# C-01_CPU_PWR.net
KiCad netlist of a schematic drawn in Altium Designer
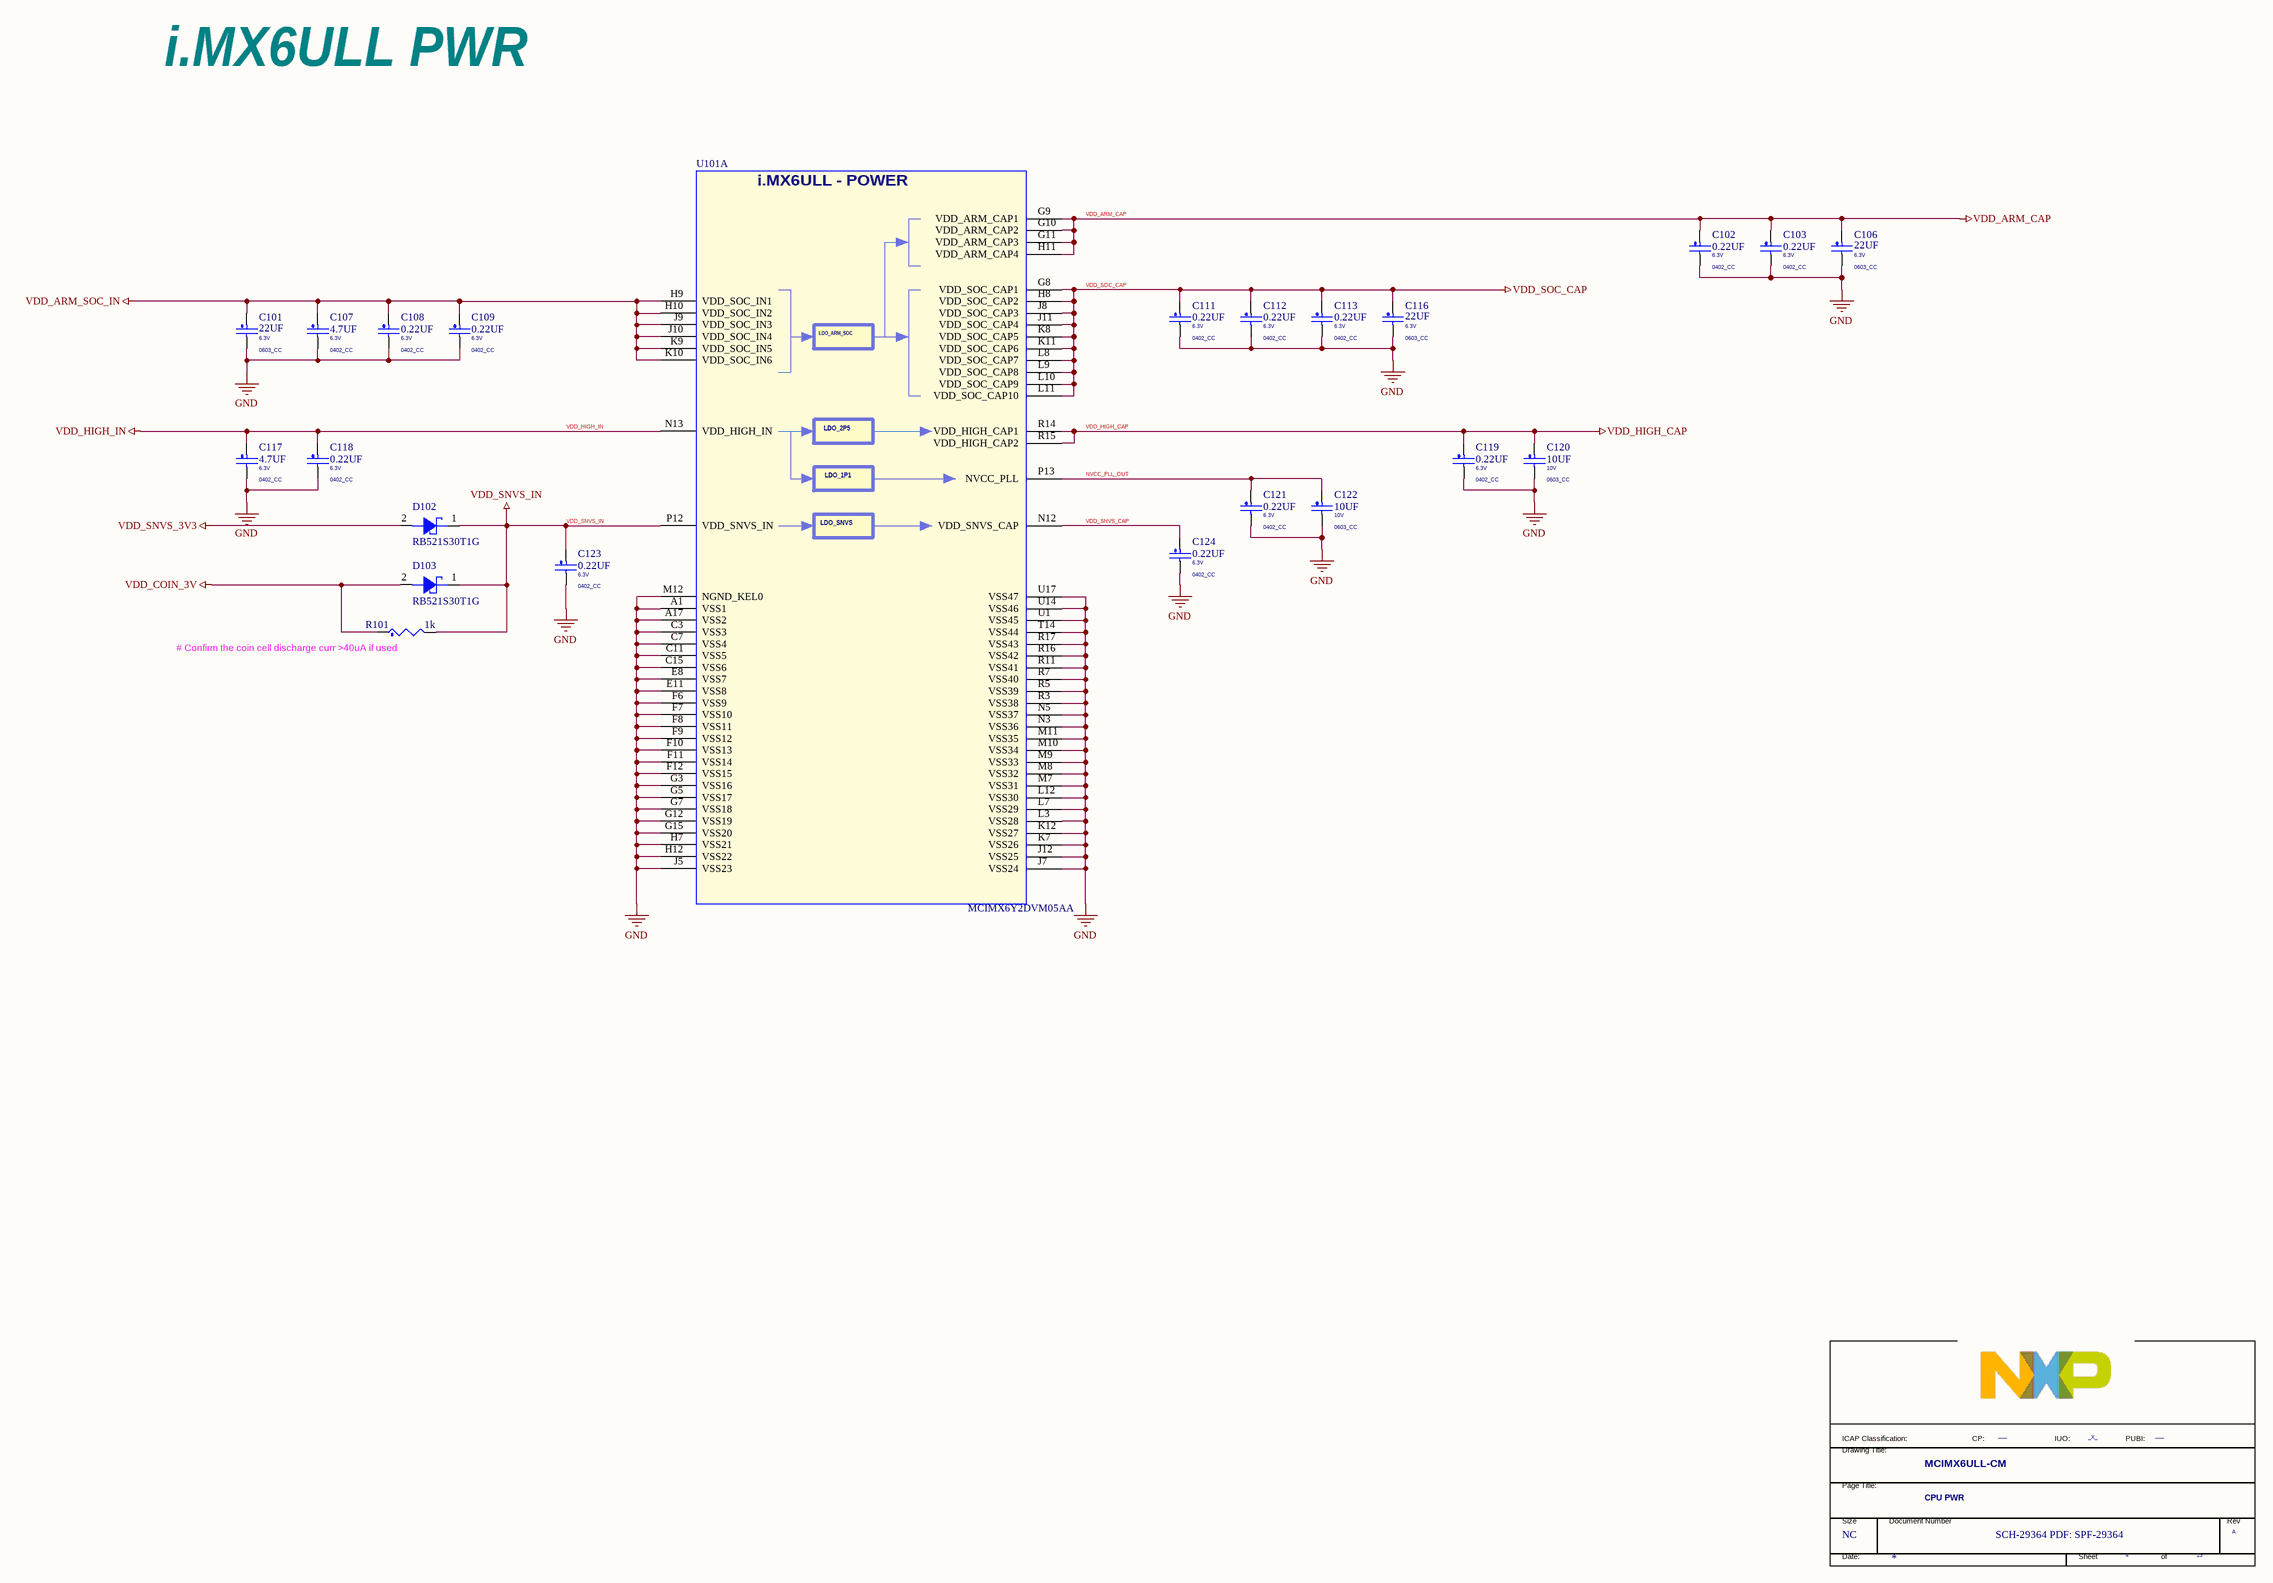
[diagram p0: C-01 CPU PWR.SchDoc]

(export (version "E")
  (design (tool "Eeschema 10.0.6"))
  (components
    (comp (ref "C101")
      (value "22UF")
      (footprint "C0603_H0.8mm")
      (description "CAP CER 22UF 6.3V 20% X5R 0603")
      (fields
        (field (name "VOLTAGE") "6.3V")
        (field (name "TOLERANCE") "20%")
        (field (name "VOLTAGE RATING") "6.3V")
        (field (name "PCB FOOTPRINT") "0603_CC")
      )
      (libsource (lib "*") (part "CAP_NP"))
    )
    (comp (ref "C102")
      (value "0.22UF")
      (footprint "C0402_H0.5mm")
      (description "CAP CER 0.22UF 6.3V 20% X5R 0402")
      (fields
        (field (name "VOLTAGE") "6.3V")
        (field (name "TOLERANCE") "20%")
        (field (name "PCB FOOTPRINT") "0402_CC")
      )
      (libsource (lib "*") (part "CAP_NP"))
    )
    (comp (ref "C103")
      (value "0.22UF")
      (footprint "C0402_H0.5mm")
      (description "CAP CER 0.22UF 6.3V 20% X5R 0402")
      (fields
        (field (name "VOLTAGE") "6.3V")
        (field (name "TOLERANCE") "20%")
        (field (name "PCB FOOTPRINT") "0402_CC")
      )
      (libsource (lib "*") (part "CAP_NP"))
    )
    (comp (ref "C106")
      (value "22UF")
      (footprint "C0603_H0.8mm")
      (description "CAP CER 22UF 6.3V 20% X5R 0603")
      (fields
        (field (name "VOLTAGE") "6.3V")
        (field (name "TOLERANCE") "20%")
        (field (name "PCB FOOTPRINT") "0603_CC")
      )
      (libsource (lib "*") (part "CAP_NP"))
    )
    (comp (ref "C107")
      (value "4.7UF")
      (footprint "C0402_H0.5mm")
      (description "CAP CER 4.7UF 6.3V 20% X5R 0402")
      (fields
        (field (name "TOLERANCE") "20%")
        (field (name "VOLTAGE RATING") "6.3V")
        (field (name "VOLTAGE") "6.3V")
        (field (name "PCB FOOTPRINT") "0402_CC")
      )
      (libsource (lib "*") (part "CAP_NP"))
    )
    (comp (ref "C108")
      (value "0.22UF")
      (footprint "C0402_H0.5mm")
      (description "CAP CER 0.22UF 6.3V 20% X5R 0402")
      (fields
        (field (name "VOLTAGE") "6.3V")
        (field (name "TOLERANCE") "20%")
        (field (name "PCB FOOTPRINT") "0402_CC")
      )
      (libsource (lib "*") (part "CAP_NP"))
    )
    (comp (ref "C109")
      (value "0.22UF")
      (footprint "C0402_H0.5mm")
      (description "CAP CER 0.22UF 6.3V 20% X5R 0402")
      (fields
        (field (name "VOLTAGE") "6.3V")
        (field (name "TOLERANCE") "20%")
        (field (name "PCB FOOTPRINT") "0402_CC")
      )
      (libsource (lib "*") (part "CAP_NP"))
    )
    (comp (ref "C111")
      (value "0.22UF")
      (footprint "C0402_H0.5mm")
      (description "CAP CER 0.22UF 6.3V 20% X5R 0402")
      (fields
        (field (name "TOLERANCE") "20%")
        (field (name "VOLTAGE") "6.3V")
        (field (name "PCB FOOTPRINT") "0402_CC")
      )
      (libsource (lib "*") (part "CAP_NP"))
    )
    (comp (ref "C112")
      (value "0.22UF")
      (footprint "C0402_H0.5mm")
      (description "CAP CER 0.22UF 6.3V 20% X5R 0402")
      (fields
        (field (name "TOLERANCE") "20%")
        (field (name "VOLTAGE") "6.3V")
        (field (name "PCB FOOTPRINT") "0402_CC")
      )
      (libsource (lib "*") (part "CAP_NP"))
    )
    (comp (ref "C113")
      (value "0.22UF")
      (footprint "C0402_H0.5mm")
      (description "CAP CER 0.22UF 6.3V 20% X5R 0402")
      (fields
        (field (name "TOLERANCE") "20%")
        (field (name "VOLTAGE") "6.3V")
        (field (name "PCB FOOTPRINT") "0402_CC")
      )
      (libsource (lib "*") (part "CAP_NP"))
    )
    (comp (ref "C116")
      (value "22UF")
      (footprint "C0603_H0.8mm")
      (description "CAP CER 22UF 6.3V 20% X5R 0603")
      (fields
        (field (name "TOLERANCE") "20%")
        (field (name "VOLTAGE") "6.3V")
        (field (name "PCB FOOTPRINT") "0603_CC")
      )
      (libsource (lib "*") (part "CAP_NP"))
    )
    (comp (ref "C117")
      (value "4.7UF")
      (footprint "C0402_H0.5mm")
      (description "CAP CER 4.7UF 6.3V 20% X5R 0402")
      (fields
        (field (name "TOLERANCE") "20%")
        (field (name "VOLTAGE RATING") "6.3V")
        (field (name "VOLTAGE") "6.3V")
        (field (name "PCB FOOTPRINT") "0402_CC")
      )
      (libsource (lib "*") (part "CAP_NP"))
    )
    (comp (ref "C118")
      (value "0.22UF")
      (footprint "C0402_H0.5mm")
      (description "CAP CER 0.22UF 6.3V 20% X5R 0402")
      (fields
        (field (name "VOLTAGE") "6.3V")
        (field (name "TOLERANCE") "20%")
        (field (name "PCB FOOTPRINT") "0402_CC")
      )
      (libsource (lib "*") (part "CAP_NP"))
    )
    (comp (ref "C119")
      (value "0.22UF")
      (footprint "C0402_H0.5mm")
      (description "CAP CER 0.22UF 6.3V 20% X5R 0402")
      (fields
        (field (name "VOLTAGE") "6.3V")
        (field (name "TOLERANCE") "20%")
        (field (name "PCB FOOTPRINT") "0402_CC")
      )
      (libsource (lib "*") (part "CAP_NP"))
    )
    (comp (ref "C120")
      (value "10UF")
      (footprint "C0603_H0.8mm")
      (description "CAP CER 10UF 10V 20% X5R 0603")
      (fields (field (name "VOLTAGE") "10V") (field (name "PCB FOOTPRINT") "0603_CC"))
      (libsource (lib "*") (part "CAP_NP"))
    )
    (comp (ref "C121")
      (value "0.22UF")
      (footprint "C0402_H0.5mm")
      (description "CAP CER 0.22UF 6.3V 20% X5R 0402")
      (fields
        (field (name "TOLERANCE") "20%")
        (field (name "VOLTAGE") "6.3V")
        (field (name "PCB FOOTPRINT") "0402_CC")
      )
      (libsource (lib "*") (part "CAP_NP"))
    )
    (comp (ref "C122")
      (value "10UF")
      (footprint "C0603_H0.8mm")
      (description "CAP CER 10UF 10V 20% X5R 0603")
      (fields (field (name "VOLTAGE") "10V") (field (name "PCB FOOTPRINT") "0603_CC"))
      (libsource (lib "*") (part "CAP_NP"))
    )
    (comp (ref "C123")
      (value "0.22UF")
      (footprint "C0402_H0.5mm")
      (description "CAP CER 0.22UF 6.3V 20% X5R 0402")
      (fields
        (field (name "VOLTAGE") "6.3V")
        (field (name "TOLERANCE") "20%")
        (field (name "PCB FOOTPRINT") "0402_CC")
      )
      (libsource (lib "*") (part "CAP_NP"))
    )
    (comp (ref "C124")
      (value "0.22UF")
      (footprint "C0402_H0.5mm")
      (description "CAP CER 0.22UF 6.3V 20% X5R 0402")
      (fields
        (field (name "TOLERANCE") "20%")
        (field (name "VOLTAGE") "6.3V")
        (field (name "PCB FOOTPRINT") "0402_CC")
      )
      (libsource (lib "*") (part "CAP_NP"))
    )
    (comp (ref "D102")
      (value "RB521S30T1G")
      (footprint "SOD-523_1.2x0.8mm")
      (description "DIODE SCH 200MA 30V AEC-Q101 SOD-523")
      (libsource (lib "*") (part "DIODE_SCHTKY"))
    )
    (comp (ref "D103")
      (value "RB521S30T1G")
      (footprint "SOD-523_1.2x0.8mm")
      (description "DIODE SCH 200MA 30V AEC-Q101 SOD-523")
      (libsource (lib "*") (part "DIODE_SCHTKY"))
    )
    (comp (ref "R101")
      (value "1k")
      (footprint "R0402_H0.35mm")
      (description "RES MF 1.0K 1/16W 5% 0402")
      (fields (field (name "TOLERANCE") "5%"))
      (libsource (lib "*") (part "RES"))
    )
    (comp (ref "U101")
      (value "MCIMX6Y2DVM05AA")
      (footprint "BGA289_14x14mm")
      (description "IC CPU ARM COREA7 528MHZ 16BIT 1.5V PBGA289")
      (libsource (lib "*") (part "MCIMX6Y2DVM05AA_PBGA_289P"))
    )
  )
  (nets
    (net (code "1") (name "/NVCC_PLL_OUT") (class "Default")
      (node (ref "C121") (pin "1") (pinfunction "1_1") (pintype "passive"))
      (node (ref "C122") (pin "1") (pinfunction "1_1") (pintype "passive"))
      (node (ref "U101") (pin "P13") (pinfunction "NVCC_PLL_P13") (pintype "power_in"))
    )
    (net (code "2") (name "/VDD_SNVS_CAP") (class "Default")
      (node (ref "C124") (pin "1") (pinfunction "1_1") (pintype "passive"))
      (node (ref "U101") (pin "N12") (pinfunction "VDD_SNVS_CAP_N12") (pintype "power_in"))
    )
    (net (code "3") (name "GND") (class "Default")
      (node (ref "C101") (pin "2") (pinfunction "2_2") (pintype "passive"))
      (node (ref "C102") (pin "2") (pinfunction "2_2") (pintype "passive"))
      (node (ref "C103") (pin "2") (pinfunction "2_2") (pintype "passive"))
      (node (ref "C106") (pin "2") (pinfunction "2_2") (pintype "passive"))
      (node (ref "C107") (pin "2") (pinfunction "2_2") (pintype "passive"))
      (node (ref "C108") (pin "2") (pinfunction "2_2") (pintype "passive"))
      (node (ref "C109") (pin "2") (pinfunction "2_2") (pintype "passive"))
      (node (ref "C111") (pin "2") (pinfunction "2_2") (pintype "passive"))
      (node (ref "C112") (pin "2") (pinfunction "2_2") (pintype "passive"))
      (node (ref "C113") (pin "2") (pinfunction "2_2") (pintype "passive"))
      (node (ref "C116") (pin "2") (pinfunction "2_2") (pintype "passive"))
      (node (ref "C117") (pin "2") (pinfunction "2_2") (pintype "passive"))
      (node (ref "C118") (pin "2") (pinfunction "2_2") (pintype "passive"))
      (node (ref "C119") (pin "2") (pinfunction "2_2") (pintype "passive"))
      (node (ref "C120") (pin "2") (pinfunction "2_2") (pintype "passive"))
      (node (ref "C121") (pin "2") (pinfunction "2_2") (pintype "passive"))
      (node (ref "C122") (pin "2") (pinfunction "2_2") (pintype "passive"))
      (node (ref "C123") (pin "2") (pinfunction "2_2") (pintype "passive"))
      (node (ref "C124") (pin "2") (pinfunction "2_2") (pintype "passive"))
      (node (ref "U101") (pin "A1") (pinfunction "VSS1_A1") (pintype "power_in"))
      (node (ref "U101") (pin "A17") (pinfunction "VSS2_A17") (pintype "power_in"))
      (node (ref "U101") (pin "C11") (pinfunction "VSS5_C11") (pintype "power_in"))
      (node (ref "U101") (pin "C15") (pinfunction "VSS6_C15") (pintype "power_in"))
      (node (ref "U101") (pin "C3") (pinfunction "VSS3_C3") (pintype "power_in"))
      (node (ref "U101") (pin "C7") (pinfunction "VSS4_C7") (pintype "power_in"))
      (node (ref "U101") (pin "E11") (pinfunction "VSS8_E11") (pintype "power_in"))
      (node (ref "U101") (pin "E8") (pinfunction "VSS7_E8") (pintype "power_in"))
      (node (ref "U101") (pin "F10") (pinfunction "VSS13_F10") (pintype "power_in"))
      (node (ref "U101") (pin "F11") (pinfunction "VSS14_F11") (pintype "power_in"))
      (node (ref "U101") (pin "F12") (pinfunction "VSS15_F12") (pintype "power_in"))
      (node (ref "U101") (pin "F6") (pinfunction "VSS9_F6") (pintype "power_in"))
      (node (ref "U101") (pin "F7") (pinfunction "VSS10_F7") (pintype "power_in"))
      (node (ref "U101") (pin "F8") (pinfunction "VSS11_F8") (pintype "power_in"))
      (node (ref "U101") (pin "F9") (pinfunction "VSS12_F9") (pintype "power_in"))
      (node (ref "U101") (pin "G12") (pinfunction "VSS19_G12") (pintype "power_in"))
      (node (ref "U101") (pin "G15") (pinfunction "VSS20_G15") (pintype "power_in"))
      (node (ref "U101") (pin "G3") (pinfunction "VSS16_G3") (pintype "power_in"))
      (node (ref "U101") (pin "G5") (pinfunction "VSS17_G5") (pintype "power_in"))
      (node (ref "U101") (pin "G7") (pinfunction "VSS18_G7") (pintype "power_in"))
      (node (ref "U101") (pin "H12") (pinfunction "VSS22_H12") (pintype "power_in"))
      (node (ref "U101") (pin "H7") (pinfunction "VSS21_H7") (pintype "power_in"))
      (node (ref "U101") (pin "J12") (pinfunction "VSS25_J12") (pintype "power_in"))
      (node (ref "U101") (pin "J5") (pinfunction "VSS23_J5") (pintype "power_in"))
      (node (ref "U101") (pin "J7") (pinfunction "VSS24_J7") (pintype "power_in"))
      (node (ref "U101") (pin "K12") (pinfunction "VSS27_K12") (pintype "power_in"))
      (node (ref "U101") (pin "K7") (pinfunction "VSS26_K7") (pintype "power_in"))
      (node (ref "U101") (pin "L12") (pinfunction "VSS30_L12") (pintype "power_in"))
      (node (ref "U101") (pin "L3") (pinfunction "VSS28_L3") (pintype "power_in"))
      (node (ref "U101") (pin "L7") (pinfunction "VSS29_L7") (pintype "power_in"))
      (node (ref "U101") (pin "M10") (pinfunction "VSS34_M10") (pintype "power_in"))
      (node (ref "U101") (pin "M11") (pinfunction "VSS35_M11") (pintype "power_in"))
      (node (ref "U101") (pin "M12") (pinfunction "NGND_KEL0_M12") (pintype "power_in"))
      (node (ref "U101") (pin "M7") (pinfunction "VSS31_M7") (pintype "power_in"))
      (node (ref "U101") (pin "M8") (pinfunction "VSS32_M8") (pintype "power_in"))
      (node (ref "U101") (pin "M9") (pinfunction "VSS33_M9") (pintype "power_in"))
      (node (ref "U101") (pin "N3") (pinfunction "VSS36_N3") (pintype "power_in"))
      (node (ref "U101") (pin "N5") (pinfunction "VSS37_N5") (pintype "power_in"))
      (node (ref "U101") (pin "R11") (pinfunction "VSS41_R11") (pintype "power_in"))
      (node (ref "U101") (pin "R16") (pinfunction "VSS42_R16") (pintype "power_in"))
      (node (ref "U101") (pin "R17") (pinfunction "VSS43_R17") (pintype "power_in"))
      (node (ref "U101") (pin "R3") (pinfunction "VSS38_R3") (pintype "power_in"))
      (node (ref "U101") (pin "R5") (pinfunction "VSS39_R5") (pintype "power_in"))
      (node (ref "U101") (pin "R7") (pinfunction "VSS40_R7") (pintype "power_in"))
      (node (ref "U101") (pin "T14") (pinfunction "VSS44_T14") (pintype "power_in"))
      (node (ref "U101") (pin "U1") (pinfunction "VSS45_U1") (pintype "power_in"))
      (node (ref "U101") (pin "U14") (pinfunction "VSS46_U14") (pintype "power_in"))
      (node (ref "U101") (pin "U17") (pinfunction "VSS47_U17") (pintype "power_in"))
    )
    (net (code "4") (name "VDD_ARM_CAP") (class "Default")
      (node (ref "C102") (pin "1") (pinfunction "1_1") (pintype "passive"))
      (node (ref "C103") (pin "1") (pinfunction "1_1") (pintype "passive"))
      (node (ref "C106") (pin "1") (pinfunction "1_1") (pintype "passive"))
      (node (ref "U101") (pin "G10") (pinfunction "VDD_ARM_CAP2_G10") (pintype "power_in"))
      (node (ref "U101") (pin "G11") (pinfunction "VDD_ARM_CAP3_G11") (pintype "power_in"))
      (node (ref "U101") (pin "G9") (pinfunction "VDD_ARM_CAP1_G9") (pintype "power_in"))
      (node (ref "U101") (pin "H11") (pinfunction "VDD_ARM_CAP4_H11") (pintype "power_in"))
    )
    (net (code "5") (name "VDD_ARM_SOC_IN") (class "Default")
      (node (ref "C101") (pin "1") (pinfunction "1_1") (pintype "passive"))
      (node (ref "C107") (pin "1") (pinfunction "1_1") (pintype "passive"))
      (node (ref "C108") (pin "1") (pinfunction "1_1") (pintype "passive"))
      (node (ref "C109") (pin "1") (pinfunction "1_1") (pintype "passive"))
      (node (ref "U101") (pin "H10") (pinfunction "VDD_SOC_IN2_H10") (pintype "power_in"))
      (node (ref "U101") (pin "H9") (pinfunction "VDD_SOC_IN1_H9") (pintype "power_in"))
      (node (ref "U101") (pin "J10") (pinfunction "VDD_SOC_IN4_J10") (pintype "power_in"))
      (node (ref "U101") (pin "J9") (pinfunction "VDD_SOC_IN3_J9") (pintype "power_in"))
      (node (ref "U101") (pin "K10") (pinfunction "VDD_SOC_IN6_K10") (pintype "power_in"))
      (node (ref "U101") (pin "K9") (pinfunction "VDD_SOC_IN5_K9") (pintype "power_in"))
    )
    (net (code "6") (name "VDD_COIN_3V") (class "Default")
      (node (ref "D103") (pin "2") (pinfunction "A_2") (pintype "passive"))
      (node (ref "R101") (pin "1") (pinfunction "1_1") (pintype "passive"))
    )
    (net (code "7") (name "VDD_HIGH_CAP") (class "Default")
      (node (ref "C119") (pin "1") (pinfunction "1_1") (pintype "passive"))
      (node (ref "C120") (pin "1") (pinfunction "1_1") (pintype "passive"))
      (node (ref "U101") (pin "R14") (pinfunction "VDD_HIGH_CAP1_R14") (pintype "power_in"))
      (node (ref "U101") (pin "R15") (pinfunction "VDD_HIGH_CAP2_R15") (pintype "power_in"))
    )
    (net (code "8") (name "VDD_HIGH_IN") (class "Default")
      (node (ref "C117") (pin "1") (pinfunction "1_1") (pintype "passive"))
      (node (ref "C118") (pin "1") (pinfunction "1_1") (pintype "passive"))
      (node (ref "U101") (pin "N13") (pinfunction "VDD_HIGH_IN_N13") (pintype "power_in"))
    )
    (net (code "9") (name "VDD_SNVS_3V3") (class "Default")
      (node (ref "D102") (pin "2") (pinfunction "A_2") (pintype "passive"))
    )
    (net (code "10") (name "VDD_SNVS_IN") (class "Default")
      (node (ref "C123") (pin "1") (pinfunction "1_1") (pintype "passive"))
      (node (ref "D102") (pin "1") (pinfunction "C_1") (pintype "passive"))
      (node (ref "D103") (pin "1") (pinfunction "C_1") (pintype "passive"))
      (node (ref "R101") (pin "2") (pinfunction "2_2") (pintype "passive"))
      (node (ref "U101") (pin "P12") (pinfunction "VDD_SNVS_IN_P12") (pintype "power_in"))
    )
    (net (code "11") (name "VDD_SOC_CAP") (class "Default")
      (node (ref "C111") (pin "1") (pinfunction "1_1") (pintype "passive"))
      (node (ref "C112") (pin "1") (pinfunction "1_1") (pintype "passive"))
      (node (ref "C113") (pin "1") (pinfunction "1_1") (pintype "passive"))
      (node (ref "C116") (pin "1") (pinfunction "1_1") (pintype "passive"))
      (node (ref "U101") (pin "G8") (pinfunction "VDD_SOC_CAP1_G8") (pintype "power_in"))
      (node (ref "U101") (pin "H8") (pinfunction "VDD_SOC_CAP2_H8") (pintype "power_in"))
      (node (ref "U101") (pin "J11") (pinfunction "VDD_SOC_CAP4_J11") (pintype "power_in"))
      (node (ref "U101") (pin "J8") (pinfunction "VDD_SOC_CAP3_J8") (pintype "power_in"))
      (node (ref "U101") (pin "K11") (pinfunction "VDD_SOC_CAP6_K11") (pintype "power_in"))
      (node (ref "U101") (pin "K8") (pinfunction "VDD_SOC_CAP5_K8") (pintype "power_in"))
      (node (ref "U101") (pin "L10") (pinfunction "VDD_SOC_CAP9_L10") (pintype "power_in"))
      (node (ref "U101") (pin "L11") (pinfunction "VDD_SOC_CAP10_L11") (pintype "power_in"))
      (node (ref "U101") (pin "L8") (pinfunction "VDD_SOC_CAP7_L8") (pintype "power_in"))
      (node (ref "U101") (pin "L9") (pinfunction "VDD_SOC_CAP8_L9") (pintype "power_in"))
    )
  )
)
